# 05_mPCIe.net
KiCad netlist of a schematic drawn in Altium Designer
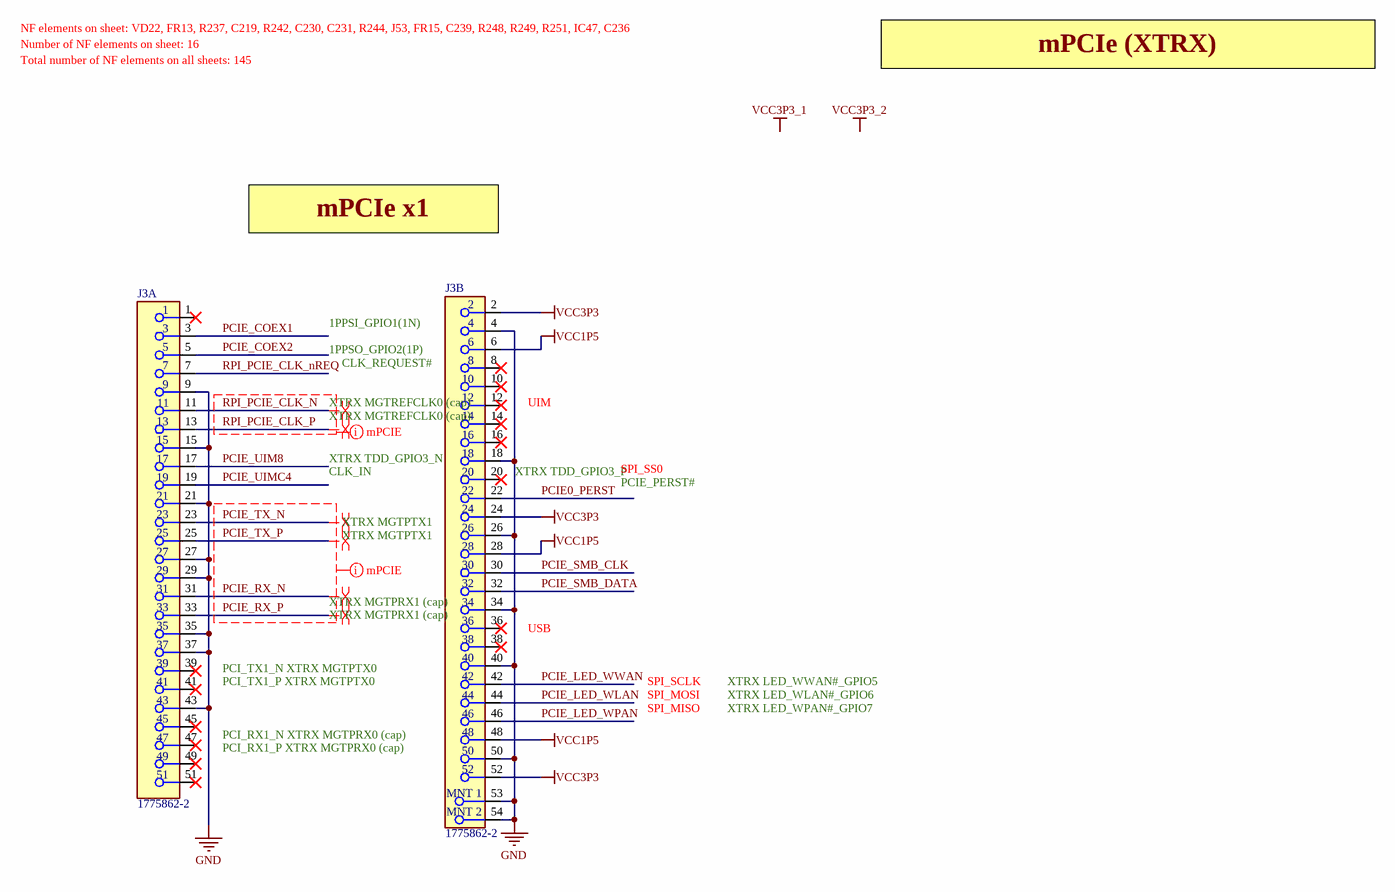
[diagram p0: 05_mPCIe.SchDoc]

(export (version "E")
  (design (tool "Eeschema 10.0.6"))
  (components
    (comp (ref "J3")
      (value "1775862-2")
      (footprint "MiniPCIe_connector_XTRX")
      (description "CONN PCI EXP MINI FEMALE 52POS")
      (fields (field (name "MANUFACTURER") "TE Connectivity AMP"))
      (libsource (lib "LimeMicroAltiumLib_schLib_r04") (part "MINI_PCIE_FEMALE"))
    )
  )
  (nets
    (net (code "1") (name "/PCIE0_PERST") (class "Default")
      (node (ref "J3") (pin "22") (pinfunction "22_22") (pintype "passive"))
    )
    (net (code "2") (name "/PCIE_COEX1") (class "Default")
      (node (ref "J3") (pin "3") (pinfunction "3_3") (pintype "passive"))
    )
    (net (code "3") (name "/PCIE_COEX2") (class "Default")
      (node (ref "J3") (pin "5") (pinfunction "5_5") (pintype "passive"))
    )
    (net (code "4") (name "/PCIE_LED_WLAN") (class "Default")
      (node (ref "J3") (pin "44") (pinfunction "44_44") (pintype "passive"))
    )
    (net (code "5") (name "/PCIE_LED_WPAN") (class "Default")
      (node (ref "J3") (pin "46") (pinfunction "46_46") (pintype "passive"))
    )
    (net (code "6") (name "/PCIE_LED_WWAN") (class "Default")
      (node (ref "J3") (pin "42") (pinfunction "42_42") (pintype "passive"))
    )
    (net (code "7") (name "/PCIE_RX_N") (class "Default")
      (node (ref "J3") (pin "31") (pinfunction "31_31") (pintype "passive"))
    )
    (net (code "8") (name "/PCIE_RX_P") (class "Default")
      (node (ref "J3") (pin "33") (pinfunction "33_33") (pintype "passive"))
    )
    (net (code "9") (name "/PCIE_SMB_CLK") (class "Default")
      (node (ref "J3") (pin "30") (pinfunction "30_30") (pintype "passive"))
    )
    (net (code "10") (name "/PCIE_SMB_DATA") (class "Default")
      (node (ref "J3") (pin "32") (pinfunction "32_32") (pintype "passive"))
    )
    (net (code "11") (name "/PCIE_TX_N") (class "Default")
      (node (ref "J3") (pin "23") (pinfunction "23_23") (pintype "passive"))
    )
    (net (code "12") (name "/PCIE_TX_P") (class "Default")
      (node (ref "J3") (pin "25") (pinfunction "25_25") (pintype "passive"))
    )
    (net (code "13") (name "/PCIE_UIM8") (class "Default")
      (node (ref "J3") (pin "17") (pinfunction "17_17") (pintype "passive"))
    )
    (net (code "14") (name "/PCIE_UIMC4") (class "Default")
      (node (ref "J3") (pin "19") (pinfunction "19_19") (pintype "passive"))
    )
    (net (code "15") (name "/RPI_PCIE_CLK_N") (class "Default")
      (node (ref "J3") (pin "11") (pinfunction "11_11") (pintype "passive"))
    )
    (net (code "16") (name "/RPI_PCIE_CLK_P") (class "Default")
      (node (ref "J3") (pin "13") (pinfunction "13_13") (pintype "passive"))
    )
    (net (code "17") (name "/RPI_PCIE_CLK_nREQ") (class "Default")
      (node (ref "J3") (pin "7") (pinfunction "7_7") (pintype "passive"))
    )
    (net (code "18") (name "GND") (class "Default")
      (node (ref "J3") (pin "15") (pinfunction "15_15") (pintype "passive"))
      (node (ref "J3") (pin "18") (pinfunction "18_18") (pintype "passive"))
      (node (ref "J3") (pin "21") (pinfunction "21_21") (pintype "passive"))
      (node (ref "J3") (pin "26") (pinfunction "26_26") (pintype "passive"))
      (node (ref "J3") (pin "27") (pinfunction "27_27") (pintype "passive"))
      (node (ref "J3") (pin "29") (pinfunction "29_29") (pintype "passive"))
      (node (ref "J3") (pin "34") (pinfunction "34_34") (pintype "passive"))
      (node (ref "J3") (pin "35") (pinfunction "35_35") (pintype "passive"))
      (node (ref "J3") (pin "37") (pinfunction "37_37") (pintype "passive"))
      (node (ref "J3") (pin "4") (pinfunction "4_4") (pintype "passive"))
      (node (ref "J3") (pin "40") (pinfunction "40_40") (pintype "passive"))
      (node (ref "J3") (pin "43") (pinfunction "43_43") (pintype "passive"))
      (node (ref "J3") (pin "50") (pinfunction "50_50") (pintype "passive"))
      (node (ref "J3") (pin "53") (pinfunction "MNT_1_53") (pintype "passive"))
      (node (ref "J3") (pin "54") (pinfunction "MNT_2_54") (pintype "passive"))
      (node (ref "J3") (pin "9") (pinfunction "9_9") (pintype "passive"))
    )
    (net (code "19") (name "VCC1P5") (class "Default")
      (node (ref "J3") (pin "28") (pinfunction "28_28") (pintype "passive"))
      (node (ref "J3") (pin "48") (pinfunction "48_48") (pintype "passive"))
      (node (ref "J3") (pin "6") (pinfunction "6_6") (pintype "passive"))
    )
    (net (code "20") (name "VCC3P3") (class "Default")
      (node (ref "J3") (pin "2") (pinfunction "2_2") (pintype "passive"))
      (node (ref "J3") (pin "24") (pinfunction "24_24") (pintype "passive"))
      (node (ref "J3") (pin "52") (pinfunction "52_52") (pintype "passive"))
    )
    (net (code "23") (name "unconnected-(J3-Pad1)") (class "Default")
      (node (ref "J3") (pin "1") (pinfunction "1_1") (pintype "passive+no_connect"))
    )
    (net (code "24") (name "unconnected-(J3-Pad8)") (class "Default")
      (node (ref "J3") (pin "8") (pinfunction "8_8") (pintype "passive+no_connect"))
    )
    (net (code "25") (name "unconnected-(J3-Pad10)") (class "Default")
      (node (ref "J3") (pin "10") (pinfunction "10_10") (pintype "passive+no_connect"))
    )
    (net (code "26") (name "unconnected-(J3-Pad12)") (class "Default")
      (node (ref "J3") (pin "12") (pinfunction "12_12") (pintype "passive+no_connect"))
    )
    (net (code "27") (name "unconnected-(J3-Pad14)") (class "Default")
      (node (ref "J3") (pin "14") (pinfunction "14_14") (pintype "passive+no_connect"))
    )
    (net (code "28") (name "unconnected-(J3-Pad16)") (class "Default")
      (node (ref "J3") (pin "16") (pinfunction "16_16") (pintype "passive+no_connect"))
    )
    (net (code "29") (name "unconnected-(J3-Pad20)") (class "Default")
      (node (ref "J3") (pin "20") (pinfunction "20_20") (pintype "passive+no_connect"))
    )
    (net (code "30") (name "unconnected-(J3-Pad36)") (class "Default")
      (node (ref "J3") (pin "36") (pinfunction "36_36") (pintype "passive+no_connect"))
    )
    (net (code "31") (name "unconnected-(J3-Pad38)") (class "Default")
      (node (ref "J3") (pin "38") (pinfunction "38_38") (pintype "passive+no_connect"))
    )
    (net (code "32") (name "unconnected-(J3-Pad39)") (class "Default")
      (node (ref "J3") (pin "39") (pinfunction "39_39") (pintype "passive+no_connect"))
    )
    (net (code "33") (name "unconnected-(J3-Pad41)") (class "Default")
      (node (ref "J3") (pin "41") (pinfunction "41_41") (pintype "passive+no_connect"))
    )
    (net (code "34") (name "unconnected-(J3-Pad45)") (class "Default")
      (node (ref "J3") (pin "45") (pinfunction "45_45") (pintype "passive+no_connect"))
    )
    (net (code "35") (name "unconnected-(J3-Pad47)") (class "Default")
      (node (ref "J3") (pin "47") (pinfunction "47_47") (pintype "passive+no_connect"))
    )
    (net (code "36") (name "unconnected-(J3-Pad49)") (class "Default")
      (node (ref "J3") (pin "49") (pinfunction "49_49") (pintype "passive+no_connect"))
    )
    (net (code "37") (name "unconnected-(J3-Pad51)") (class "Default")
      (node (ref "J3") (pin "51") (pinfunction "51_51") (pintype "passive+no_connect"))
    )
  )
)
